# Master.net
KiCad netlist of a schematic drawn in EAGLE
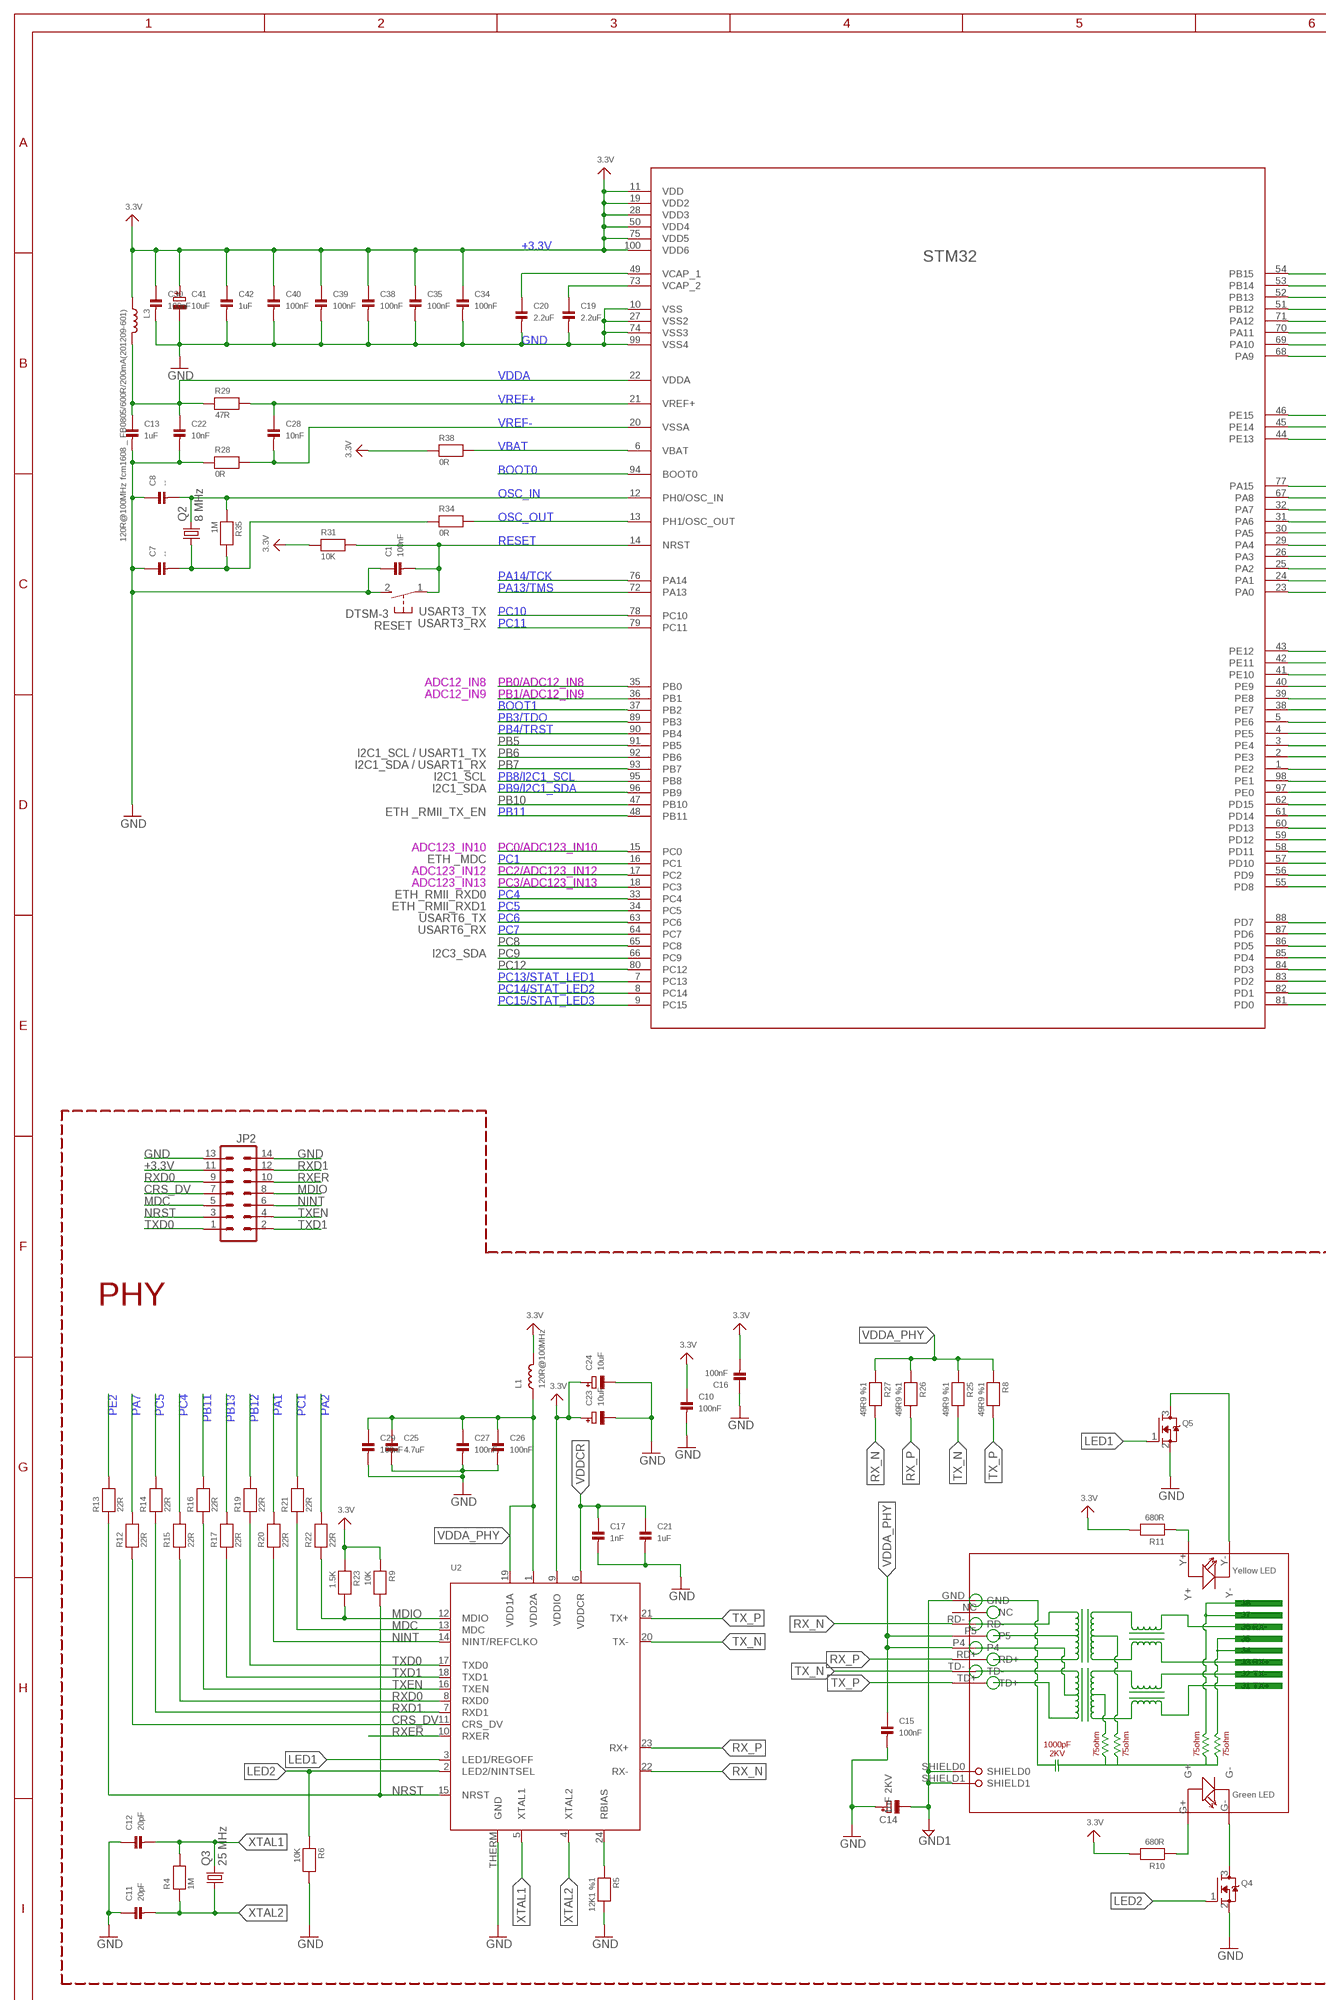
[diagram p0: schematic, sheet 1, part 1 of 2]
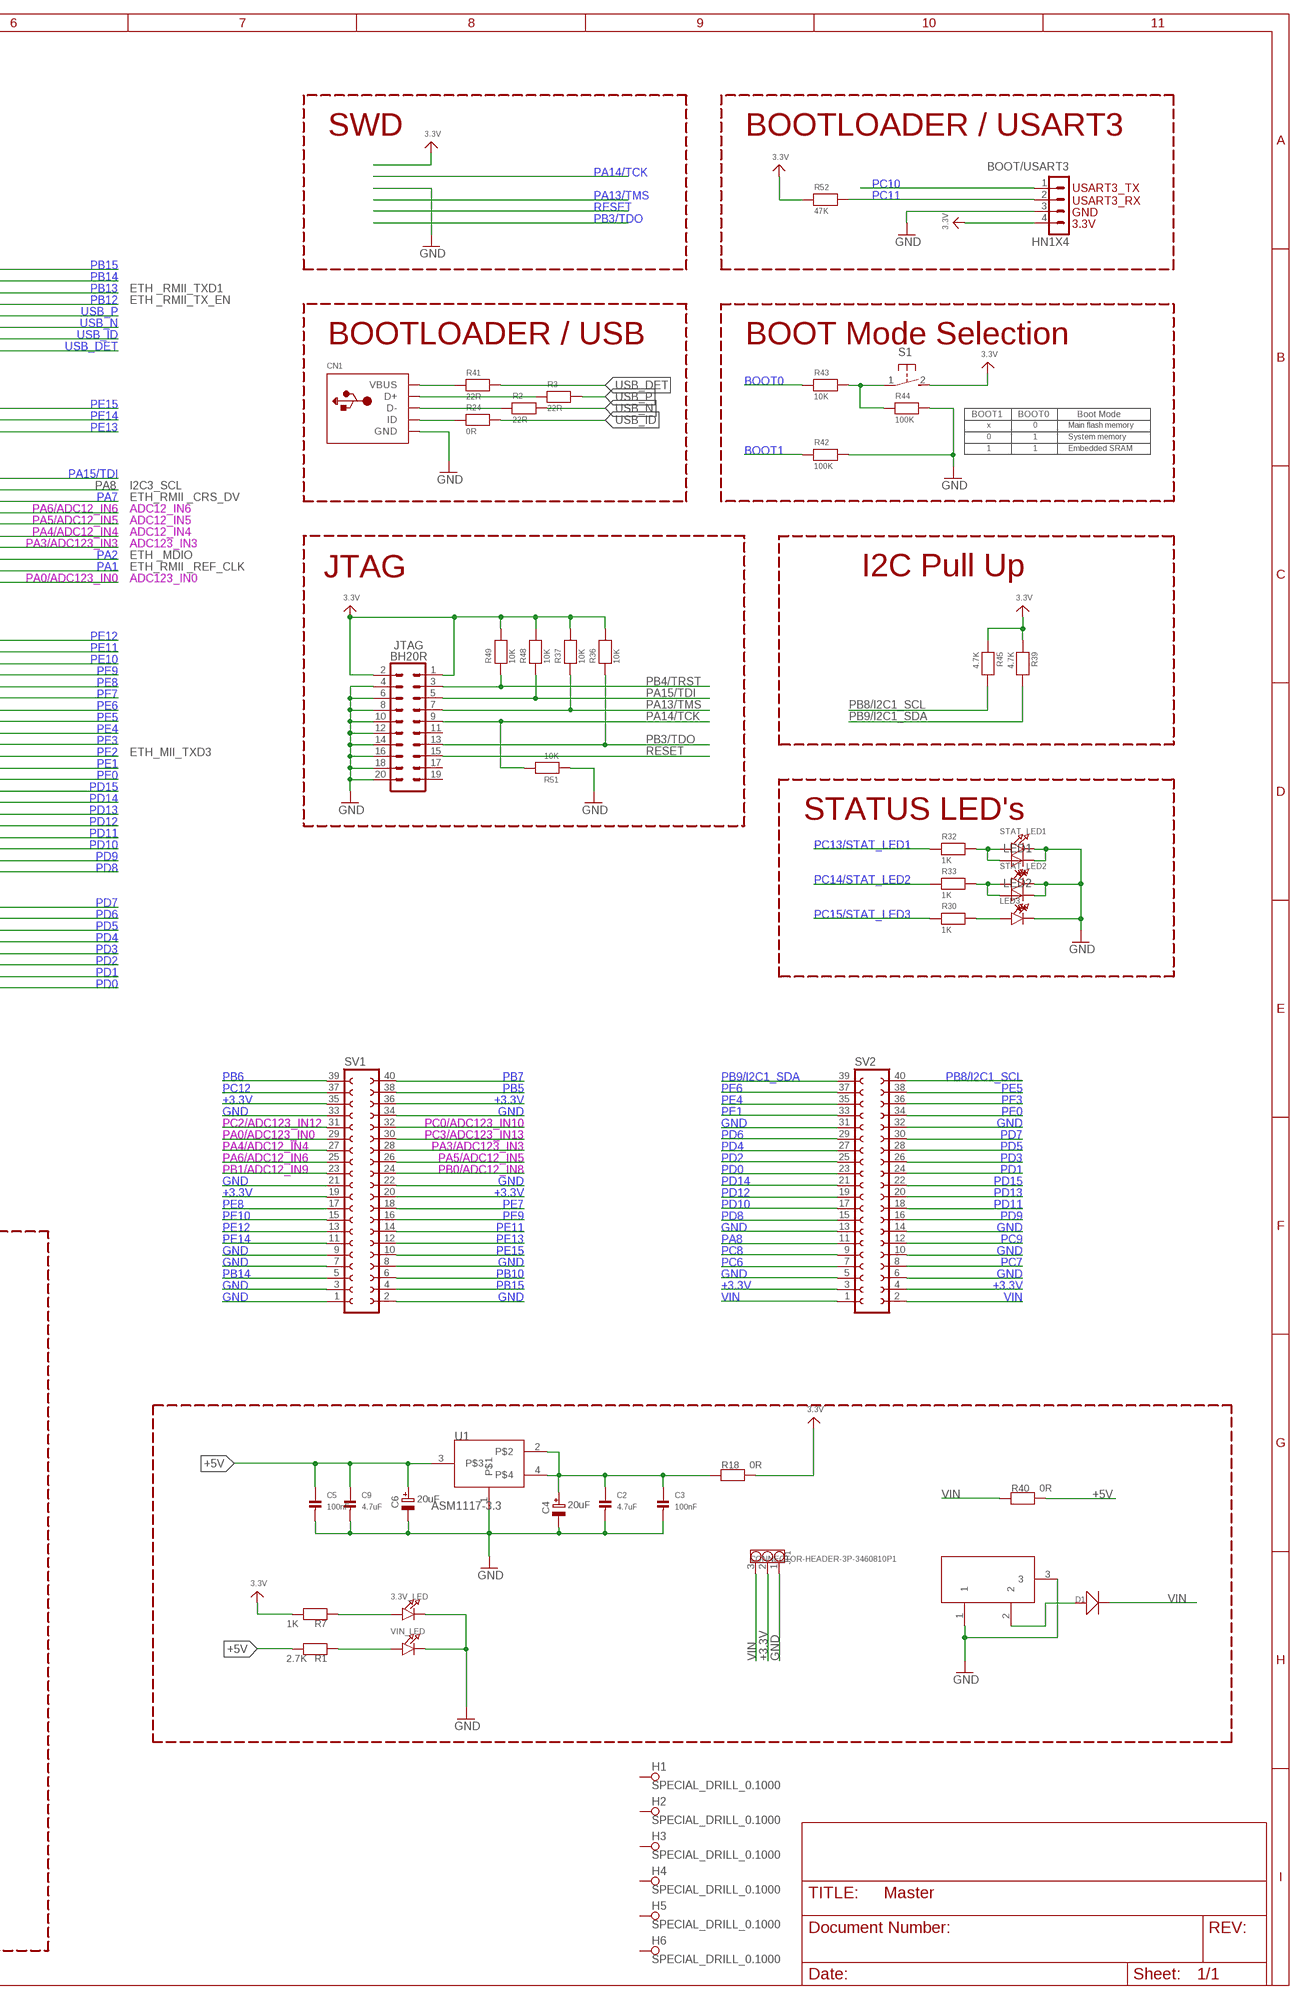
[diagram p1: schematic, sheet 1, part 2 of 2]

(export (version "E")
  (design (tool "Eeschema 10.0.6"))
  (components
    (comp (ref "3.3V_LED")
      (value "LED0805")
      (footprint "eagle-import:CHIPLED_0805")
      (libsource (lib "eagle-import") (part "LED0805"))
    )
    (comp (ref "BOOT/USART3")
      (value "HN1X4")
      (footprint "eagle-import:HN1X4")
      (libsource (lib "eagle-import") (part "CON4HN1X4"))
    )
    (comp (ref "C1")
      (value "100nF")
      (footprint "eagle-import:_0603")
      (libsource (lib "eagle-import") (part "CAP_CERAMIC_0603"))
    )
    (comp (ref "C2")
      (value "4.7uF")
      (footprint "eagle-import:0805")
      (libsource (lib "eagle-import") (part "CAP_CERAMIC0805"))
    )
    (comp (ref "C3")
      (value "100nF")
      (footprint "eagle-import:0805")
      (libsource (lib "eagle-import") (part "CAP_CERAMIC0805"))
    )
    (comp (ref "C4")
      (value "20uF")
      (footprint "eagle-import:EIA3528-21_B-R")
      (libsource (lib "eagle-import") (part "CAP_TANTALUMB/3528_REFLOW"))
    )
    (comp (ref "C5")
      (value "100nF")
      (footprint "eagle-import:0805")
      (libsource (lib "eagle-import") (part "CAP_CERAMIC0805"))
    )
    (comp (ref "C6")
      (value "20uF")
      (footprint "eagle-import:EIA3528-21_B-R")
      (libsource (lib "eagle-import") (part "CAP_TANTALUMB/3528_REFLOW"))
    )
    (comp (ref "C7")
      (value "--")
      (footprint "eagle-import:_0603")
      (libsource (lib "eagle-import") (part "CAP_CERAMIC_0603"))
    )
    (comp (ref "C8")
      (value "--")
      (footprint "eagle-import:_0603")
      (libsource (lib "eagle-import") (part "CAP_CERAMIC_0603"))
    )
    (comp (ref "C9")
      (value "4.7uF")
      (footprint "eagle-import:0805")
      (libsource (lib "eagle-import") (part "CAP_CERAMIC0805"))
    )
    (comp (ref "C10")
      (value "100nF")
      (footprint "eagle-import:_0603")
      (libsource (lib "eagle-import") (part "CAP_CERAMIC_0603"))
    )
    (comp (ref "C11")
      (value "20pF")
      (footprint "eagle-import:_0603")
      (libsource (lib "eagle-import") (part "CAP_CERAMIC_0603"))
    )
    (comp (ref "C12")
      (value "20pF")
      (footprint "eagle-import:_0603")
      (libsource (lib "eagle-import") (part "CAP_CERAMIC_0603"))
    )
    (comp (ref "C13")
      (value "1uF")
      (footprint "eagle-import:_0805")
      (libsource (lib "eagle-import") (part "CAP_CERAMIC_0805"))
    )
    (comp (ref "C14")
      (value "1nF 2KV")
      (footprint "eagle-import:EIA3528-21_B-R")
      (libsource (lib "eagle-import") (part "CAP_TANTALUMB/3528_REFLOW"))
    )
    (comp (ref "C15")
      (value "100nF")
      (footprint "eagle-import:_0805")
      (libsource (lib "eagle-import") (part "CAP_CERAMIC_0805"))
    )
    (comp (ref "C16")
      (value "100nF")
      (footprint "eagle-import:_0603")
      (libsource (lib "eagle-import") (part "CAP_CERAMIC_0603"))
    )
    (comp (ref "C17")
      (value "1nF")
      (footprint "eagle-import:_0603")
      (libsource (lib "eagle-import") (part "CAP_CERAMIC_0603"))
    )
    (comp (ref "C19")
      (value "2.2uF")
      (footprint "eagle-import:1206")
      (libsource (lib "eagle-import") (part "CAP_CERAMIC1206"))
    )
    (comp (ref "C20")
      (value "2.2uF")
      (footprint "eagle-import:1206")
      (libsource (lib "eagle-import") (part "CAP_CERAMIC1206"))
    )
    (comp (ref "C21")
      (value "1uF")
      (footprint "eagle-import:_0805")
      (libsource (lib "eagle-import") (part "CAP_CERAMIC_0805"))
    )
    (comp (ref "C22")
      (value "10nF")
      (footprint "eagle-import:_0603")
      (libsource (lib "eagle-import") (part "CAP_CERAMIC_0603"))
    )
    (comp (ref "C23")
      (value "10uF")
      (footprint "eagle-import:EIA3528-21_B-R")
      (libsource (lib "eagle-import") (part "CAP_TANTALUMB/3528_REFLOW"))
    )
    (comp (ref "C24")
      (value "10uF")
      (footprint "eagle-import:EIA3528-21_B-R")
      (libsource (lib "eagle-import") (part "CAP_TANTALUMB/3528_REFLOW"))
    )
    (comp (ref "C25")
      (value "4.7uF")
      (footprint "eagle-import:_0805")
      (libsource (lib "eagle-import") (part "CAP_CERAMIC_0805"))
    )
    (comp (ref "C26")
      (value "100nF")
      (footprint "eagle-import:_0603")
      (libsource (lib "eagle-import") (part "CAP_CERAMIC_0603"))
    )
    (comp (ref "C27")
      (value "100nF")
      (footprint "eagle-import:_0603")
      (libsource (lib "eagle-import") (part "CAP_CERAMIC_0603"))
    )
    (comp (ref "C28")
      (value "10nF")
      (footprint "eagle-import:_0603")
      (libsource (lib "eagle-import") (part "CAP_CERAMIC_0603"))
    )
    (comp (ref "C29")
      (value "100nF")
      (footprint "eagle-import:_0603")
      (libsource (lib "eagle-import") (part "CAP_CERAMIC_0603"))
    )
    (comp (ref "C30")
      (value "100nF")
      (footprint "eagle-import:_0603")
      (libsource (lib "eagle-import") (part "CAP_CERAMIC_0603"))
    )
    (comp (ref "C34")
      (value "100nF")
      (footprint "eagle-import:_0603")
      (libsource (lib "eagle-import") (part "CAP_CERAMIC_0603"))
    )
    (comp (ref "C35")
      (value "100nF")
      (footprint "eagle-import:_0603")
      (libsource (lib "eagle-import") (part "CAP_CERAMIC_0603"))
    )
    (comp (ref "C38")
      (value "100nF")
      (footprint "eagle-import:_0603")
      (libsource (lib "eagle-import") (part "CAP_CERAMIC_0603"))
    )
    (comp (ref "C39")
      (value "100nF")
      (footprint "eagle-import:_0603")
      (libsource (lib "eagle-import") (part "CAP_CERAMIC_0603"))
    )
    (comp (ref "C40")
      (value "100nF")
      (footprint "eagle-import:_0603")
      (libsource (lib "eagle-import") (part "CAP_CERAMIC_0603"))
    )
    (comp (ref "C41")
      (value "10uF")
      (footprint "eagle-import:EIA3528-21_B-R")
      (libsource (lib "eagle-import") (part "CAP_TANTALUMB/3528_REFLOW"))
    )
    (comp (ref "C42")
      (value "1uF")
      (footprint "eagle-import:_0805")
      (libsource (lib "eagle-import") (part "CAP_CERAMIC_0805"))
    )
    (comp (ref "CN1")
      (value "USBMINIBLARGE")
      (footprint "eagle-import:USB-MINIB_LARGER")
      (libsource (lib "eagle-import") (part "USBMINIBLARGE"))
    )
    (comp (ref "D1")
      (value "D-D1206")
      (footprint "eagle-import:LL-34")
      (libsource (lib "eagle-import") (part "D-D1206"))
    )
    (comp (ref "H1")
      (value "SPECIAL_DRILL_0.1000")
      (footprint "eagle-import:PAD_0.1000")
      (libsource (lib "eagle-import") (part "SPECIAL_DRILL_0.1000"))
    )
    (comp (ref "H2")
      (value "SPECIAL_DRILL_0.1000")
      (footprint "eagle-import:PAD_0.1000")
      (libsource (lib "eagle-import") (part "SPECIAL_DRILL_0.1000"))
    )
    (comp (ref "H3")
      (value "SPECIAL_DRILL_0.1000")
      (footprint "eagle-import:PAD_0.1000")
      (libsource (lib "eagle-import") (part "SPECIAL_DRILL_0.1000"))
    )
    (comp (ref "H4")
      (value "SPECIAL_DRILL_0.1000")
      (footprint "eagle-import:PAD_0.1000")
      (libsource (lib "eagle-import") (part "SPECIAL_DRILL_0.1000"))
    )
    (comp (ref "H5")
      (value "SPECIAL_DRILL_0.1000")
      (footprint "eagle-import:PAD_0.1000")
      (libsource (lib "eagle-import") (part "SPECIAL_DRILL_0.1000"))
    )
    (comp (ref "H6")
      (value "SPECIAL_DRILL_0.1000")
      (footprint "eagle-import:PAD_0.1000")
      (libsource (lib "eagle-import") (part "SPECIAL_DRILL_0.1000"))
    )
    (comp (ref "JP1")
      (value "CONNECTOR-HEADER-3P-3460810P1")
      (footprint "eagle-import:1X3P-2.54-2.54-11.6-3.0-BLACK-MALE")
      (libsource (lib "eagle-import") (part "CONNECTOR-HEADER-3P-3460810P1"))
    )
    (comp (ref "JP2")
      (value "MA07-2")
      (footprint "eagle-import:MA07-2")
      (libsource (lib "eagle-import") (part "MA07-2"))
    )
    (comp (ref "JTAG")
      (value "BH20R")
      (footprint "eagle-import:BH20R")
      (libsource (lib "eagle-import") (part "ML20R"))
    )
    (comp (ref "L1")
      (value "120R@100MHz")
      (footprint "eagle-import:_0805")
      (libsource (lib "eagle-import") (part "INDUCTOR_0805"))
    )
    (comp (ref "L3")
      (value "120R@100MHz fcm1608 _ FB0805/600R/200mA(201209-601)")
      (footprint "eagle-import:_0805")
      (libsource (lib "eagle-import") (part "INDUCTOR_0805"))
    )
    (comp (ref "LED1")
      (value "LED5MM")
      (footprint "eagle-import:LED5MM")
      (libsource (lib "eagle-import") (part "LED5MM"))
    )
    (comp (ref "LED2")
      (value "LED5MM")
      (footprint "eagle-import:LED5MM")
      (libsource (lib "eagle-import") (part "LED5MM"))
    )
    (comp (ref "LED3")
      (value "LED0805")
      (footprint "eagle-import:CHIPLED_0805")
      (libsource (lib "eagle-import") (part "LED0805"))
    )
    (comp (ref "Q2")
      (value "8 MHz")
      (footprint "eagle-import:HC49UP")
      (libsource (lib "eagle-import") (part "CRYSTALHC49UP"))
    )
    (comp (ref "Q3")
      (value "25 MHz")
      (footprint "eagle-import:HC49UP")
      (libsource (lib "eagle-import") (part "CRYSTALHC49UP"))
    )
    (comp (ref "Q4")
      (value "MOSFET-NWIDE")
      (footprint "eagle-import:SOT23-WIDE")
      (libsource (lib "eagle-import") (part "MOSFET-NWIDE"))
    )
    (comp (ref "Q5")
      (value "MOSFET-NWIDE")
      (footprint "eagle-import:SOT23-WIDE")
      (libsource (lib "eagle-import") (part "MOSFET-NWIDE"))
    )
    (comp (ref "R1")
      (value "2.7K")
      (footprint "eagle-import:_0603")
      (libsource (lib "eagle-import") (part "RESISTOR_0603"))
    )
    (comp (ref "R2")
      (value "22R")
      (footprint "eagle-import:_0603")
      (libsource (lib "eagle-import") (part "RESISTOR_0603"))
    )
    (comp (ref "R3")
      (value "22R")
      (footprint "eagle-import:_0603")
      (libsource (lib "eagle-import") (part "RESISTOR_0603"))
    )
    (comp (ref "R4")
      (value "1M")
      (footprint "eagle-import:_0603")
      (libsource (lib "eagle-import") (part "RESISTOR_0603"))
    )
    (comp (ref "R5")
      (value "12K1 %1")
      (footprint "eagle-import:_0603")
      (libsource (lib "eagle-import") (part "RESISTOR_0603"))
    )
    (comp (ref "R6")
      (value "10K")
      (footprint "eagle-import:_0603")
      (libsource (lib "eagle-import") (part "RESISTOR_0603"))
    )
    (comp (ref "R7")
      (value "1K")
      (footprint "eagle-import:_0603")
      (libsource (lib "eagle-import") (part "RESISTOR_0603"))
    )
    (comp (ref "R8")
      (value "49R9 %1")
      (footprint "eagle-import:_0603")
      (libsource (lib "eagle-import") (part "RESISTOR_0603"))
    )
    (comp (ref "R9")
      (value "10K")
      (footprint "eagle-import:_0603")
      (libsource (lib "eagle-import") (part "RESISTOR_0603"))
    )
    (comp (ref "R10")
      (value "680R")
      (footprint "eagle-import:_0805")
      (libsource (lib "eagle-import") (part "RESISTOR_0805"))
    )
    (comp (ref "R11")
      (value "680R")
      (footprint "eagle-import:_0805")
      (libsource (lib "eagle-import") (part "RESISTOR_0805"))
    )
    (comp (ref "R12")
      (value "22R")
      (footprint "eagle-import:_0603")
      (libsource (lib "eagle-import") (part "RESISTOR_0603"))
    )
    (comp (ref "R13")
      (value "22R")
      (footprint "eagle-import:_0603")
      (libsource (lib "eagle-import") (part "RESISTOR_0603"))
    )
    (comp (ref "R14")
      (value "22R")
      (footprint "eagle-import:_0603")
      (libsource (lib "eagle-import") (part "RESISTOR_0603"))
    )
    (comp (ref "R15")
      (value "22R")
      (footprint "eagle-import:_0603")
      (libsource (lib "eagle-import") (part "RESISTOR_0603"))
    )
    (comp (ref "R16")
      (value "22R")
      (footprint "eagle-import:_0603")
      (libsource (lib "eagle-import") (part "RESISTOR_0603"))
    )
    (comp (ref "R17")
      (value "22R")
      (footprint "eagle-import:_0603")
      (libsource (lib "eagle-import") (part "RESISTOR_0603"))
    )
    (comp (ref "R18")
      (value "0R")
      (footprint "eagle-import:0805")
      (libsource (lib "eagle-import") (part "RESISTOR0805"))
    )
    (comp (ref "R19")
      (value "22R")
      (footprint "eagle-import:_0603")
      (libsource (lib "eagle-import") (part "RESISTOR_0603"))
    )
    (comp (ref "R20")
      (value "22R")
      (footprint "eagle-import:_0603")
      (libsource (lib "eagle-import") (part "RESISTOR_0603"))
    )
    (comp (ref "R21")
      (value "22R")
      (footprint "eagle-import:_0603")
      (libsource (lib "eagle-import") (part "RESISTOR_0603"))
    )
    (comp (ref "R22")
      (value "22R")
      (footprint "eagle-import:_0603")
      (libsource (lib "eagle-import") (part "RESISTOR_0603"))
    )
    (comp (ref "R23")
      (value "1.5K")
      (footprint "eagle-import:_0603")
      (libsource (lib "eagle-import") (part "RESISTOR_0603"))
    )
    (comp (ref "R24")
      (value "0R")
      (footprint "eagle-import:_0603")
      (libsource (lib "eagle-import") (part "RESISTOR_0603"))
    )
    (comp (ref "R25")
      (value "49R9 %1")
      (footprint "eagle-import:_0603")
      (libsource (lib "eagle-import") (part "RESISTOR_0603"))
    )
    (comp (ref "R26")
      (value "49R9 %1")
      (footprint "eagle-import:_0603")
      (libsource (lib "eagle-import") (part "RESISTOR_0603"))
    )
    (comp (ref "R27")
      (value "49R9 %1")
      (footprint "eagle-import:_0603")
      (libsource (lib "eagle-import") (part "RESISTOR_0603"))
    )
    (comp (ref "R28")
      (value "0R")
      (footprint "eagle-import:_0603")
      (libsource (lib "eagle-import") (part "RESISTOR_0603"))
    )
    (comp (ref "R29")
      (value "47R")
      (footprint "eagle-import:_0603")
      (libsource (lib "eagle-import") (part "RESISTOR_0603"))
    )
    (comp (ref "R30")
      (value "1K")
      (footprint "eagle-import:_0603")
      (libsource (lib "eagle-import") (part "RESISTOR_0603"))
    )
    (comp (ref "R31")
      (value "10K")
      (footprint "eagle-import:_0603")
      (libsource (lib "eagle-import") (part "RESISTOR_0603"))
    )
    (comp (ref "R32")
      (value "1K")
      (footprint "eagle-import:_0603")
      (libsource (lib "eagle-import") (part "RESISTOR_0603"))
    )
    (comp (ref "R33")
      (value "1K")
      (footprint "eagle-import:_0603")
      (libsource (lib "eagle-import") (part "RESISTOR_0603"))
    )
    (comp (ref "R34")
      (value "0R")
      (footprint "eagle-import:_0603")
      (libsource (lib "eagle-import") (part "RESISTOR_0603"))
    )
    (comp (ref "R35")
      (value "1M")
      (footprint "eagle-import:_0603")
      (libsource (lib "eagle-import") (part "RESISTOR_0603"))
    )
    (comp (ref "R36")
      (value "10K")
      (footprint "eagle-import:_0603")
      (libsource (lib "eagle-import") (part "RESISTOR_0603"))
    )
    (comp (ref "R37")
      (value "10K")
      (footprint "eagle-import:_0603")
      (libsource (lib "eagle-import") (part "RESISTOR_0603"))
    )
    (comp (ref "R38")
      (value "0R")
      (footprint "eagle-import:_0603")
      (libsource (lib "eagle-import") (part "RESISTOR_0603"))
    )
    (comp (ref "R39")
      (value "4.7K")
      (footprint "eagle-import:1206")
      (libsource (lib "eagle-import") (part "RESISTOR1206"))
    )
    (comp (ref "R40")
      (value "0R")
      (footprint "eagle-import:0805")
      (libsource (lib "eagle-import") (part "RESISTOR0805"))
    )
    (comp (ref "R41")
      (value "22R")
      (footprint "eagle-import:_0603")
      (libsource (lib "eagle-import") (part "RESISTOR_0603"))
    )
    (comp (ref "R42")
      (value "100K")
      (footprint "eagle-import:_0603")
      (libsource (lib "eagle-import") (part "RESISTOR_0603"))
    )
    (comp (ref "R43")
      (value "10K")
      (footprint "eagle-import:_0603")
      (libsource (lib "eagle-import") (part "RESISTOR_0603"))
    )
    (comp (ref "R44")
      (value "100K")
      (footprint "eagle-import:_0603")
      (libsource (lib "eagle-import") (part "RESISTOR_0603"))
    )
    (comp (ref "R45")
      (value "4.7K")
      (footprint "eagle-import:1206")
      (libsource (lib "eagle-import") (part "RESISTOR1206"))
    )
    (comp (ref "R48")
      (value "10K")
      (footprint "eagle-import:_0603")
      (libsource (lib "eagle-import") (part "RESISTOR_0603"))
    )
    (comp (ref "R49")
      (value "10K")
      (footprint "eagle-import:_0603")
      (libsource (lib "eagle-import") (part "RESISTOR_0603"))
    )
    (comp (ref "R51")
      (value "10K")
      (footprint "eagle-import:_0603")
      (libsource (lib "eagle-import") (part "RESISTOR_0603"))
    )
    (comp (ref "R52")
      (value "47K")
      (footprint "eagle-import:_0603")
      (libsource (lib "eagle-import") (part "RESISTOR_0603"))
    )
    (comp (ref "RESET")
      (value "DTSM-3")
      (footprint "eagle-import:DTSM-3")
      (libsource (lib "eagle-import") (part "DTSM-3"))
    )
    (comp (ref "RJ1")
      (value "HR911105A")
      (footprint "eagle-import:HR911105A")
      (libsource (lib "eagle-import") (part "HR911105A"))
    )
    (comp (ref "S1")
      (value "31-XX")
      (footprint "eagle-import:B3F-31XX")
      (fields (field (name "MPN") "B3F-3100"))
      (libsource (lib "eagle-import") (part "31-XX"))
    )
    (comp (ref "STAT_LED1")
      (value "LED0805")
      (footprint "eagle-import:CHIPLED_0805")
      (libsource (lib "eagle-import") (part "LED0805"))
    )
    (comp (ref "STAT_LED2")
      (value "LED0805")
      (footprint "eagle-import:CHIPLED_0805")
      (libsource (lib "eagle-import") (part "LED0805"))
    )
    (comp (ref "STM32")
      (value "STM32F407")
      (footprint "eagle-import:100LQFP")
      (libsource (lib "eagle-import") (part "STM32F407"))
    )
    (comp (ref "SV1")
      (value "FE20-2")
      (footprint "eagle-import:FE20-2")
      (libsource (lib "eagle-import") (part "FE20-2"))
    )
    (comp (ref "SV2")
      (value "FE20-2")
      (footprint "eagle-import:FE20-2")
      (libsource (lib "eagle-import") (part "FE20-2"))
    )
    (comp (ref "U1")
      (value "ASM1117-3.3")
      (footprint "eagle-import:SOT223")
      (libsource (lib "eagle-import") (part "ASM1117-3.3"))
    )
    (comp (ref "U2")
      (value "LAN8720")
      (footprint "eagle-import:QFN24_4MM")
      (libsource (lib "eagle-import") (part "LAN8720"))
    )
    (comp (ref "VIN_LED")
      (value "LED0805")
      (footprint "eagle-import:CHIPLED_0805")
      (libsource (lib "eagle-import") (part "LED0805"))
    )
    (comp (ref "X1")
      (value "DC21MMX")
      (footprint "eagle-import:DC-21MM")
      (libsource (lib "eagle-import") (part "DC21MMX"))
    )
  )
  (nets
    (net (code "1") (name "+5V") (class "Default")
      (node (ref "C5") (pin "1") (pinfunction "P$1_1") (pintype "passive"))
      (node (ref "C6") (pin "+") (pinfunction "+_+") (pintype "passive"))
      (node (ref "C9") (pin "1") (pinfunction "P$1_1") (pintype "passive"))
      (node (ref "R1") (pin "2") (pinfunction "2_2") (pintype "passive"))
      (node (ref "R40") (pin "2") (pinfunction "2_2") (pintype "passive"))
      (node (ref "U1") (pin "3") (pinfunction "P$3_3") (pintype "bidirectional"))
    )
    (net (code "2") (name "/BOOT0") (class "Default")
      (node (ref "R43") (pin "1") (pinfunction "1_1") (pintype "passive"))
      (node (ref "STM32") (pin "94") (pinfunction "BOOT0_94") (pintype "bidirectional"))
    )
    (net (code "3") (name "/BOOT1") (class "Default")
      (node (ref "R42") (pin "1") (pinfunction "1_1") (pintype "passive"))
      (node (ref "STM32") (pin "37") (pinfunction "PB2_37") (pintype "bidirectional"))
    )
    (net (code "4") (name "/CRS_DV") (class "Default")
      (node (ref "JP2") (pin "7") (pinfunction "7_7") (pintype "passive"))
      (node (ref "R12") (pin "1") (pinfunction "1_1") (pintype "passive"))
      (node (ref "U2") (pin "11") (pinfunction "CRS_DV_11") (pintype "bidirectional"))
    )
    (net (code "5") (name "/MDC") (class "Default")
      (node (ref "JP2") (pin "5") (pinfunction "5_5") (pintype "passive"))
      (node (ref "R21") (pin "1") (pinfunction "1_1") (pintype "passive"))
      (node (ref "U2") (pin "13") (pinfunction "MDC_13") (pintype "bidirectional"))
    )
    (net (code "6") (name "/MDIO") (class "Default")
      (node (ref "JP2") (pin "8") (pinfunction "8_8") (pintype "passive"))
      (node (ref "R22") (pin "1") (pinfunction "1_1") (pintype "passive"))
      (node (ref "R23") (pin "2") (pinfunction "2_2") (pintype "passive"))
      (node (ref "U2") (pin "12") (pinfunction "MDIO_12") (pintype "bidirectional"))
    )
    (net (code "7") (name "/NINT") (class "Default")
      (node (ref "JP2") (pin "6") (pinfunction "6_6") (pintype "passive"))
      (node (ref "R20") (pin "1") (pinfunction "1_1") (pintype "passive"))
      (node (ref "U2") (pin "14") (pinfunction "NINT/REFCLKO_14") (pintype "bidirectional"))
    )
    (net (code "8") (name "/NRST") (class "Default")
      (node (ref "JP2") (pin "3") (pinfunction "3_3") (pintype "passive"))
      (node (ref "R13") (pin "1") (pinfunction "1_1") (pintype "passive"))
      (node (ref "R9") (pin "2") (pinfunction "2_2") (pintype "passive"))
      (node (ref "U2") (pin "15") (pinfunction "NRST_15") (pintype "bidirectional"))
    )
    (net (code "9") (name "/OSC_IN") (class "Default")
      (node (ref "C8") (pin "2") (pinfunction "P$2_2") (pintype "passive"))
      (node (ref "Q2") (pin "2") (pinfunction "2_2") (pintype "passive"))
      (node (ref "R35") (pin "1") (pinfunction "1_1") (pintype "passive"))
      (node (ref "STM32") (pin "12") (pinfunction "PH0/OSC_IN_12") (pintype "bidirectional"))
    )
    (net (code "10") (name "/OSC_OUT") (class "Default")
      (node (ref "R34") (pin "2") (pinfunction "2_2") (pintype "passive"))
      (node (ref "STM32") (pin "13") (pinfunction "PH1/OSC_OUT_13") (pintype "bidirectional"))
    )
    (net (code "11") (name "/PA0{slash}ADC123_IN0") (class "Default")
      (node (ref "STM32") (pin "23") (pinfunction "PA0_23") (pintype "bidirectional"))
      (node (ref "SV1") (pin "29") (pinfunction "29_29") (pintype "passive"))
    )
    (net (code "12") (name "/PA1") (class "Default")
      (node (ref "R20") (pin "2") (pinfunction "2_2") (pintype "passive"))
      (node (ref "STM32") (pin "24") (pinfunction "PA1_24") (pintype "bidirectional"))
    )
    (net (code "13") (name "/PA2") (class "Default")
      (node (ref "R22") (pin "2") (pinfunction "2_2") (pintype "passive"))
      (node (ref "STM32") (pin "25") (pinfunction "PA2_25") (pintype "bidirectional"))
    )
    (net (code "14") (name "/PA3{slash}ADC123_IN3") (class "Default")
      (node (ref "STM32") (pin "26") (pinfunction "PA3_26") (pintype "bidirectional"))
      (node (ref "SV1") (pin "28") (pinfunction "28_28") (pintype "passive"))
    )
    (net (code "15") (name "/PA4{slash}ADC12_IN4") (class "Default")
      (node (ref "STM32") (pin "29") (pinfunction "PA4_29") (pintype "bidirectional"))
      (node (ref "SV1") (pin "27") (pinfunction "27_27") (pintype "passive"))
    )
    (net (code "16") (name "/PA5{slash}ADC12_IN5") (class "Default")
      (node (ref "STM32") (pin "30") (pinfunction "PA5_30") (pintype "bidirectional"))
      (node (ref "SV1") (pin "26") (pinfunction "26_26") (pintype "passive"))
    )
    (net (code "17") (name "/PA6{slash}ADC12_IN6") (class "Default")
      (node (ref "STM32") (pin "31") (pinfunction "PA6_31") (pintype "bidirectional"))
      (node (ref "SV1") (pin "25") (pinfunction "25_25") (pintype "passive"))
    )
    (net (code "18") (name "/PA7") (class "Default")
      (node (ref "R12") (pin "2") (pinfunction "2_2") (pintype "passive"))
      (node (ref "STM32") (pin "32") (pinfunction "PA7_32") (pintype "bidirectional"))
    )
    (net (code "19") (name "/PA8") (class "Default")
      (node (ref "STM32") (pin "67") (pinfunction "PA8_67") (pintype "bidirectional"))
      (node (ref "SV2") (pin "11") (pinfunction "11_11") (pintype "passive"))
    )
    (net (code "20") (name "/PA13{slash}TMS") (class "Default")
      (node (ref "JTAG") (pin "7") (pinfunction "7_7") (pintype "passive"))
      (node (ref "R37") (pin "1") (pinfunction "1_1") (pintype "passive"))
      (node (ref "STM32") (pin "72") (pinfunction "PA13_72") (pintype "bidirectional"))
    )
    (net (code "21") (name "/PA14{slash}TCK") (class "Default")
      (node (ref "JTAG") (pin "9") (pinfunction "9_9") (pintype "passive"))
      (node (ref "R51") (pin "2") (pinfunction "2_2") (pintype "passive"))
      (node (ref "STM32") (pin "76") (pinfunction "PA14_76") (pintype "bidirectional"))
    )
    (net (code "22") (name "/PA15{slash}TDI") (class "Default")
      (node (ref "JTAG") (pin "5") (pinfunction "5_5") (pintype "passive"))
      (node (ref "R48") (pin "1") (pinfunction "1_1") (pintype "passive"))
      (node (ref "STM32") (pin "77") (pinfunction "PA15_77") (pintype "bidirectional"))
    )
    (net (code "23") (name "/PB0{slash}ADC12_IN8") (class "Default")
      (node (ref "STM32") (pin "35") (pinfunction "PB0_35") (pintype "bidirectional"))
      (node (ref "SV1") (pin "24") (pinfunction "24_24") (pintype "passive"))
    )
    (net (code "24") (name "/PB1{slash}ADC12_IN9") (class "Default")
      (node (ref "STM32") (pin "36") (pinfunction "PB1_36") (pintype "bidirectional"))
      (node (ref "SV1") (pin "23") (pinfunction "23_23") (pintype "passive"))
    )
    (net (code "25") (name "/PB3{slash}TDO") (class "Default")
      (node (ref "JTAG") (pin "13") (pinfunction "13_13") (pintype "passive"))
      (node (ref "R36") (pin "1") (pinfunction "1_1") (pintype "passive"))
      (node (ref "STM32") (pin "89") (pinfunction "PB3_89") (pintype "bidirectional"))
    )
    (net (code "26") (name "/PB4{slash}TRST") (class "Default")
      (node (ref "JTAG") (pin "3") (pinfunction "3_3") (pintype "passive"))
      (node (ref "R49") (pin "1") (pinfunction "1_1") (pintype "passive"))
      (node (ref "STM32") (pin "90") (pinfunction "PB4_90") (pintype "bidirectional"))
    )
    (net (code "27") (name "/PB5") (class "Default")
      (node (ref "STM32") (pin "91") (pinfunction "PB5_91") (pintype "bidirectional"))
      (node (ref "SV1") (pin "38") (pinfunction "38_38") (pintype "passive"))
    )
    (net (code "28") (name "/PB6") (class "Default")
      (node (ref "STM32") (pin "92") (pinfunction "PB6_92") (pintype "bidirectional"))
      (node (ref "SV1") (pin "39") (pinfunction "39_39") (pintype "passive"))
    )
    (net (code "29") (name "/PB7") (class "Default")
      (node (ref "STM32") (pin "93") (pinfunction "PB7_93") (pintype "bidirectional"))
      (node (ref "SV1") (pin "40") (pinfunction "40_40") (pintype "passive"))
    )
    (net (code "30") (name "/PB8{slash}I2C1_SCL") (class "Default")
      (node (ref "R45") (pin "2") (pinfunction "2_2") (pintype "passive"))
      (node (ref "STM32") (pin "95") (pinfunction "PB8_95") (pintype "bidirectional"))
      (node (ref "SV2") (pin "40") (pinfunction "40_40") (pintype "passive"))
    )
    (net (code "31") (name "/PB9{slash}I2C1_SDA") (class "Default")
      (node (ref "R39") (pin "2") (pinfunction "2_2") (pintype "passive"))
      (node (ref "STM32") (pin "96") (pinfunction "PB9_96") (pintype "bidirectional"))
      (node (ref "SV2") (pin "39") (pinfunction "39_39") (pintype "passive"))
    )
    (net (code "32") (name "/PB10") (class "Default")
      (node (ref "STM32") (pin "47") (pinfunction "PB10_47") (pintype "bidirectional"))
      (node (ref "SV1") (pin "6") (pinfunction "6_6") (pintype "passive"))
    )
    (net (code "33") (name "/PB11") (class "Default")
      (node (ref "R16") (pin "2") (pinfunction "2_2") (pintype "passive"))
      (node (ref "STM32") (pin "48") (pinfunction "PB11_48") (pintype "bidirectional"))
    )
    (net (code "34") (name "/PB12") (class "Default")
      (node (ref "R19") (pin "2") (pinfunction "2_2") (pintype "passive"))
      (node (ref "STM32") (pin "51") (pinfunction "PB12_51") (pintype "bidirectional"))
    )
    (net (code "35") (name "/PB13") (class "Default")
      (node (ref "R17") (pin "2") (pinfunction "2_2") (pintype "passive"))
      (node (ref "STM32") (pin "52") (pinfunction "PB13_52") (pintype "bidirectional"))
    )
    (net (code "36") (name "/PB14") (class "Default")
      (node (ref "STM32") (pin "53") (pinfunction "PB14_53") (pintype "bidirectional"))
      (node (ref "SV1") (pin "5") (pinfunction "5_5") (pintype "passive"))
    )
    (net (code "37") (name "/PB15") (class "Default")
      (node (ref "STM32") (pin "54") (pinfunction "PB15_54") (pintype "bidirectional"))
      (node (ref "SV1") (pin "4") (pinfunction "4_4") (pintype "passive"))
    )
    (net (code "38") (name "/PC0{slash}ADC123_IN10") (class "Default")
      (node (ref "STM32") (pin "15") (pinfunction "PC0_15") (pintype "bidirectional"))
      (node (ref "SV1") (pin "32") (pinfunction "32_32") (pintype "passive"))
    )
    (net (code "39") (name "/PC1") (class "Default")
      (node (ref "R21") (pin "2") (pinfunction "2_2") (pintype "passive"))
      (node (ref "STM32") (pin "16") (pinfunction "PC1_16") (pintype "bidirectional"))
    )
    (net (code "40") (name "/PC2{slash}ADC123_IN12") (class "Default")
      (node (ref "STM32") (pin "17") (pinfunction "PC2_17") (pintype "bidirectional"))
      (node (ref "SV1") (pin "31") (pinfunction "31_31") (pintype "passive"))
    )
    (net (code "41") (name "/PC3{slash}ADC123_IN13") (class "Default")
      (node (ref "STM32") (pin "18") (pinfunction "PC3_18") (pintype "bidirectional"))
      (node (ref "SV1") (pin "30") (pinfunction "30_30") (pintype "passive"))
    )
    (net (code "42") (name "/PC4") (class "Default")
      (node (ref "R15") (pin "2") (pinfunction "2_2") (pintype "passive"))
      (node (ref "STM32") (pin "33") (pinfunction "PC4_33") (pintype "bidirectional"))
    )
    (net (code "43") (name "/PC5") (class "Default")
      (node (ref "R14") (pin "2") (pinfunction "2_2") (pintype "passive"))
      (node (ref "STM32") (pin "34") (pinfunction "PC5_34") (pintype "bidirectional"))
    )
    (net (code "44") (name "/PC6") (class "Default")
      (node (ref "STM32") (pin "63") (pinfunction "PC6_63") (pintype "bidirectional"))
      (node (ref "SV2") (pin "7") (pinfunction "7_7") (pintype "passive"))
    )
    (net (code "45") (name "/PC7") (class "Default")
      (node (ref "STM32") (pin "64") (pinfunction "PC7_64") (pintype "bidirectional"))
      (node (ref "SV2") (pin "8") (pinfunction "8_8") (pintype "passive"))
    )
    (net (code "46") (name "/PC8") (class "Default")
      (node (ref "STM32") (pin "65") (pinfunction "PC8_65") (pintype "bidirectional"))
      (node (ref "SV2") (pin "9") (pinfunction "9_9") (pintype "passive"))
    )
    (net (code "47") (name "/PC9") (class "Default")
      (node (ref "STM32") (pin "66") (pinfunction "PC9_66") (pintype "bidirectional"))
      (node (ref "SV2") (pin "12") (pinfunction "12_12") (pintype "passive"))
    )
    (net (code "48") (name "/PC10") (class "Default")
      (node (ref "BOOT/USART3") (pin "1") (pinfunction "1_1") (pintype "passive"))
      (node (ref "STM32") (pin "78") (pinfunction "PC10_78") (pintype "bidirectional"))
    )
    (net (code "49") (name "/PC11") (class "Default")
      (node (ref "BOOT/USART3") (pin "2") (pinfunction "2_2") (pintype "passive"))
      (node (ref "R52") (pin "2") (pinfunction "2_2") (pintype "passive"))
      (node (ref "STM32") (pin "79") (pinfunction "PC11_79") (pintype "bidirectional"))
    )
    (net (code "50") (name "/PC12") (class "Default")
      (node (ref "STM32") (pin "80") (pinfunction "PC12_80") (pintype "bidirectional"))
      (node (ref "SV1") (pin "37") (pinfunction "37_37") (pintype "passive"))
    )
    (net (code "51") (name "/PC13{slash}STAT_LED1") (class "Default")
      (node (ref "R32") (pin "1") (pinfunction "1_1") (pintype "passive"))
      (node (ref "STM32") (pin "7") (pinfunction "PC13_7") (pintype "bidirectional"))
    )
    (net (code "52") (name "/PC14{slash}STAT_LED2") (class "Default")
      (node (ref "R33") (pin "1") (pinfunction "1_1") (pintype "passive"))
      (node (ref "STM32") (pin "8") (pinfunction "PC14_8") (pintype "bidirectional"))
    )
    (net (code "53") (name "/PC15{slash}STAT_LED3") (class "Default")
      (node (ref "R30") (pin "1") (pinfunction "1_1") (pintype "passive"))
      (node (ref "STM32") (pin "9") (pinfunction "PC15_9") (pintype "bidirectional"))
    )
    (net (code "54") (name "/PD0") (class "Default")
      (node (ref "STM32") (pin "81") (pinfunction "PD0_81") (pintype "bidirectional"))
      (node (ref "SV2") (pin "23") (pinfunction "23_23") (pintype "passive"))
    )
    (net (code "55") (name "/PD1") (class "Default")
      (node (ref "STM32") (pin "82") (pinfunction "PD1_82") (pintype "bidirectional"))
      (node (ref "SV2") (pin "24") (pinfunction "24_24") (pintype "passive"))
    )
    (net (code "56") (name "/PD2") (class "Default")
      (node (ref "STM32") (pin "83") (pinfunction "PD2_83") (pintype "bidirectional"))
      (node (ref "SV2") (pin "25") (pinfunction "25_25") (pintype "passive"))
    )
    (net (code "57") (name "/PD3") (class "Default")
      (node (ref "STM32") (pin "84") (pinfunction "PD3_84") (pintype "bidirectional"))
      (node (ref "SV2") (pin "26") (pinfunction "26_26") (pintype "passive"))
    )
    (net (code "58") (name "/PD4") (class "Default")
      (node (ref "STM32") (pin "85") (pinfunction "PD4_85") (pintype "bidirectional"))
      (node (ref "SV2") (pin "27") (pinfunction "27_27") (pintype "passive"))
    )
    (net (code "59") (name "/PD5") (class "Default")
      (node (ref "STM32") (pin "86") (pinfunction "PD5_86") (pintype "bidirectional"))
      (node (ref "SV2") (pin "28") (pinfunction "28_28") (pintype "passive"))
    )
    (net (code "60") (name "/PD6") (class "Default")
      (node (ref "STM32") (pin "87") (pinfunction "PD6_87") (pintype "bidirectional"))
      (node (ref "SV2") (pin "29") (pinfunction "29_29") (pintype "passive"))
    )
    (net (code "61") (name "/PD7") (class "Default")
      (node (ref "STM32") (pin "88") (pinfunction "PD7_88") (pintype "bidirectional"))
      (node (ref "SV2") (pin "30") (pinfunction "30_30") (pintype "passive"))
    )
    (net (code "62") (name "/PD8") (class "Default")
      (node (ref "STM32") (pin "55") (pinfunction "PD8_55") (pintype "bidirectional"))
      (node (ref "SV2") (pin "15") (pinfunction "15_15") (pintype "passive"))
    )
    (net (code "63") (name "/PD9") (class "Default")
      (node (ref "STM32") (pin "56") (pinfunction "PD9_56") (pintype "bidirectional"))
      (node (ref "SV2") (pin "16") (pinfunction "16_16") (pintype "passive"))
    )
    (net (code "64") (name "/PD10") (class "Default")
      (node (ref "STM32") (pin "57") (pinfunction "PD10_57") (pintype "bidirectional"))
      (node (ref "SV2") (pin "17") (pinfunction "17_17") (pintype "passive"))
    )
    (net (code "65") (name "/PD11") (class "Default")
      (node (ref "STM32") (pin "58") (pinfunction "PD11_58") (pintype "bidirectional"))
      (node (ref "SV2") (pin "18") (pinfunction "18_18") (pintype "passive"))
    )
    (net (code "66") (name "/PD12") (class "Default")
      (node (ref "STM32") (pin "59") (pinfunction "PD12_59") (pintype "bidirectional"))
      (node (ref "SV2") (pin "19") (pinfunction "19_19") (pintype "passive"))
    )
    (net (code "67") (name "/PD13") (class "Default")
      (node (ref "STM32") (pin "60") (pinfunction "PD13_60") (pintype "bidirectional"))
      (node (ref "SV2") (pin "20") (pinfunction "20_20") (pintype "passive"))
    )
    (net (code "68") (name "/PD14") (class "Default")
      (node (ref "STM32") (pin "61") (pinfunction "PD14_61") (pintype "bidirectional"))
      (node (ref "SV2") (pin "21") (pinfunction "21_21") (pintype "passive"))
    )
    (net (code "69") (name "/PD15") (class "Default")
      (node (ref "STM32") (pin "62") (pinfunction "PD15_62") (pintype "bidirectional"))
      (node (ref "SV2") (pin "22") (pinfunction "22_22") (pintype "passive"))
    )
    (net (code "70") (name "/PE0") (class "Default")
      (node (ref "STM32") (pin "97") (pinfunction "PE0_97") (pintype "bidirectional"))
      (node (ref "SV2") (pin "34") (pinfunction "34_34") (pintype "passive"))
    )
    (net (code "71") (name "/PE1") (class "Default")
      (node (ref "STM32") (pin "98") (pinfunction "PE1_98") (pintype "bidirectional"))
      (node (ref "SV2") (pin "33") (pinfunction "33_33") (pintype "passive"))
    )
    (net (code "72") (name "/PE2") (class "Default")
      (node (ref "R13") (pin "2") (pinfunction "2_2") (pintype "passive"))
      (node (ref "STM32") (pin "1") (pinfunction "PE2_1") (pintype "bidirectional"))
    )
    (net (code "73") (name "/PE3") (class "Default")
      (node (ref "STM32") (pin "2") (pinfunction "PE3_2") (pintype "bidirectional"))
      (node (ref "SV2") (pin "36") (pinfunction "36_36") (pintype "passive"))
    )
    (net (code "74") (name "/PE4") (class "Default")
      (node (ref "STM32") (pin "3") (pinfunction "PE4_3") (pintype "bidirectional"))
      (node (ref "SV2") (pin "35") (pinfunction "35_35") (pintype "passive"))
    )
    (net (code "75") (name "/PE5") (class "Default")
      (node (ref "STM32") (pin "4") (pinfunction "PE5_4") (pintype "bidirectional"))
      (node (ref "SV2") (pin "38") (pinfunction "38_38") (pintype "passive"))
    )
    (net (code "76") (name "/PE6") (class "Default")
      (node (ref "STM32") (pin "5") (pinfunction "PE6_5") (pintype "bidirectional"))
      (node (ref "SV2") (pin "37") (pinfunction "37_37") (pintype "passive"))
    )
    (net (code "77") (name "/PE7") (class "Default")
      (node (ref "STM32") (pin "38") (pinfunction "PE7_38") (pintype "bidirectional"))
      (node (ref "SV1") (pin "18") (pinfunction "18_18") (pintype "passive"))
    )
    (net (code "78") (name "/PE8") (class "Default")
      (node (ref "STM32") (pin "39") (pinfunction "PE8_39") (pintype "bidirectional"))
      (node (ref "SV1") (pin "17") (pinfunction "17_17") (pintype "passive"))
    )
    (net (code "79") (name "/PE9") (class "Default")
      (node (ref "STM32") (pin "40") (pinfunction "PE9_40") (pintype "bidirectional"))
      (node (ref "SV1") (pin "16") (pinfunction "16_16") (pintype "passive"))
    )
    (net (code "80") (name "/PE10") (class "Default")
      (node (ref "STM32") (pin "41") (pinfunction "PE10_41") (pintype "bidirectional"))
      (node (ref "SV1") (pin "15") (pinfunction "15_15") (pintype "passive"))
    )
    (net (code "81") (name "/PE11") (class "Default")
      (node (ref "STM32") (pin "42") (pinfunction "PE11_42") (pintype "bidirectional"))
      (node (ref "SV1") (pin "14") (pinfunction "14_14") (pintype "passive"))
    )
    (net (code "82") (name "/PE12") (class "Default")
      (node (ref "STM32") (pin "43") (pinfunction "PE12_43") (pintype "bidirectional"))
      (node (ref "SV1") (pin "13") (pinfunction "13_13") (pintype "passive"))
    )
    (net (code "83") (name "/PE13") (class "Default")
      (node (ref "STM32") (pin "44") (pinfunction "PE13_44") (pintype "bidirectional"))
      (node (ref "SV1") (pin "12") (pinfunction "12_12") (pintype "passive"))
    )
    (net (code "84") (name "/PE14") (class "Default")
      (node (ref "STM32") (pin "45") (pinfunction "PE14_45") (pintype "bidirectional"))
      (node (ref "SV1") (pin "11") (pinfunction "11_11") (pintype "passive"))
    )
    (net (code "85") (name "/PE15") (class "Default")
      (node (ref "STM32") (pin "46") (pinfunction "PE15_46") (pintype "bidirectional"))
      (node (ref "SV1") (pin "10") (pinfunction "10_10") (pintype "passive"))
    )
    (net (code "86") (name "/RESET") (class "Default")
      (node (ref "C1") (pin "2") (pinfunction "P$2_2") (pintype "passive"))
      (node (ref "JTAG") (pin "15") (pinfunction "15_15") (pintype "passive"))
      (node (ref "R31") (pin "2") (pinfunction "2_2") (pintype "passive"))
      (node (ref "RESET") (pin "1") (pinfunction "1_1") (pintype "passive"))
      (node (ref "STM32") (pin "14") (pinfunction "NRST_14") (pintype "bidirectional"))
    )
    (net (code "87") (name "/RXD0") (class "Default")
      (node (ref "JP2") (pin "9") (pinfunction "9_9") (pintype "passive"))
      (node (ref "R15") (pin "1") (pinfunction "1_1") (pintype "passive"))
      (node (ref "U2") (pin "8") (pinfunction "RXD0_8") (pintype "bidirectional"))
    )
    (net (code "88") (name "/RXD1") (class "Default")
      (node (ref "JP2") (pin "12") (pinfunction "12_12") (pintype "passive"))
      (node (ref "R14") (pin "1") (pinfunction "1_1") (pintype "passive"))
      (node (ref "U2") (pin "7") (pinfunction "RXD1_7") (pintype "bidirectional"))
    )
    (net (code "89") (name "/RXER") (class "Default")
      (node (ref "JP2") (pin "10") (pinfunction "10_10") (pintype "passive"))
      (node (ref "U2") (pin "10") (pinfunction "RXER_10") (pintype "bidirectional"))
    )
    (net (code "90") (name "/TXD0") (class "Default")
      (node (ref "JP2") (pin "1") (pinfunction "1_1") (pintype "passive"))
      (node (ref "R19") (pin "1") (pinfunction "1_1") (pintype "passive"))
      (node (ref "U2") (pin "17") (pinfunction "TXD0_17") (pintype "bidirectional"))
    )
    (net (code "91") (name "/TXD1") (class "Default")
      (node (ref "JP2") (pin "2") (pinfunction "2_2") (pintype "passive"))
      (node (ref "R17") (pin "1") (pinfunction "1_1") (pintype "passive"))
      (node (ref "U2") (pin "18") (pinfunction "TXD1_18") (pintype "bidirectional"))
    )
    (net (code "92") (name "/TXEN") (class "Default")
      (node (ref "JP2") (pin "4") (pinfunction "4_4") (pintype "passive"))
      (node (ref "R16") (pin "1") (pinfunction "1_1") (pintype "passive"))
      (node (ref "U2") (pin "16") (pinfunction "TXEN_16") (pintype "bidirectional"))
    )
    (net (code "93") (name "/VBAT") (class "Default")
      (node (ref "R38") (pin "2") (pinfunction "2_2") (pintype "passive"))
      (node (ref "STM32") (pin "6") (pinfunction "VBAT_6") (pintype "bidirectional"))
    )
    (net (code "94") (name "/VDDA") (class "Default")
      (node (ref "C13") (pin "1") (pinfunction "P$1_1") (pintype "passive"))
      (node (ref "C22") (pin "1") (pinfunction "P$1_1") (pintype "passive"))
      (node (ref "L3") (pin "2") (pinfunction "2_2") (pintype "passive"))
      (node (ref "R29") (pin "1") (pinfunction "1_1") (pintype "passive"))
      (node (ref "STM32") (pin "22") (pinfunction "VDDA_22") (pintype "bidirectional"))
    )
    (net (code "95") (name "/VIN") (class "Default")
      (node (ref "D1") (pin "C") (pinfunction "-_C") (pintype "passive"))
      (node (ref "JP1") (pin "3") (pinfunction "3_3") (pintype "bidirectional"))
      (node (ref "R40") (pin "1") (pinfunction "1_1") (pintype "passive"))
      (node (ref "SV2") (pin "1") (pinfunction "1_1") (pintype "passive"))
      (node (ref "SV2") (pin "2") (pinfunction "2_2") (pintype "passive"))
    )
    (net (code "96") (name "/VREF+") (class "Default")
      (node (ref "C28") (pin "1") (pinfunction "P$1_1") (pintype "passive"))
      (node (ref "R29") (pin "2") (pinfunction "2_2") (pintype "passive"))
      (node (ref "STM32") (pin "21") (pinfunction "VREF+_21") (pintype "bidirectional"))
    )
    (net (code "97") (name "/VREF-") (class "Default")
      (node (ref "C28") (pin "2") (pinfunction "P$2_2") (pintype "passive"))
      (node (ref "R28") (pin "2") (pinfunction "2_2") (pintype "passive"))
      (node (ref "STM32") (pin "20") (pinfunction "VSSA_20") (pintype "bidirectional"))
    )
    (net (code "98") (name "3.3V") (class "Default")
      (node (ref "BOOT/USART3") (pin "4") (pinfunction "4_4") (pintype "passive"))
      (node (ref "C10") (pin "1") (pinfunction "P$1_1") (pintype "passive"))
      (node (ref "C16") (pin "2") (pinfunction "P$2_2") (pintype "passive"))
      (node (ref "C23") (pin "+") (pinfunction "+_+") (pintype "passive"))
      (node (ref "C24") (pin "+") (pinfunction "+_+") (pintype "passive"))
      (node (ref "C30") (pin "1") (pinfunction "P$1_1") (pintype "passive"))
      (node (ref "C34") (pin "1") (pinfunction "P$1_1") (pintype "passive"))
      (node (ref "C35") (pin "1") (pinfunction "P$1_1") (pintype "passive"))
      (node (ref "C38") (pin "1") (pinfunction "P$1_1") (pintype "passive"))
      (node (ref "C39") (pin "1") (pinfunction "P$1_1") (pintype "passive"))
      (node (ref "C40") (pin "1") (pinfunction "P$1_1") (pintype "passive"))
      (node (ref "C41") (pin "+") (pinfunction "+_+") (pintype "passive"))
      (node (ref "C42") (pin "1") (pinfunction "P$1_1") (pintype "passive"))
      (node (ref "JP1") (pin "2") (pinfunction "2_2") (pintype "bidirectional"))
      (node (ref "JP2") (pin "11") (pinfunction "11_11") (pintype "passive"))
      (node (ref "JTAG") (pin "1") (pinfunction "1_1") (pintype "passive"))
      (node (ref "JTAG") (pin "2") (pinfunction "2_2") (pintype "passive"))
      (node (ref "L1") (pin "2") (pinfunction "2_2") (pintype "passive"))
      (node (ref "L3") (pin "1") (pinfunction "1_1") (pintype "passive"))
      (node (ref "R10") (pin "2") (pinfunction "2_2") (pintype "passive"))
      (node (ref "R11") (pin "2") (pinfunction "2_2") (pintype "passive"))
      (node (ref "R18") (pin "2") (pinfunction "2_2") (pintype "passive"))
      (node (ref "R23") (pin "1") (pinfunction "1_1") (pintype "passive"))
      (node (ref "R31") (pin "1") (pinfunction "1_1") (pintype "passive"))
      (node (ref "R36") (pin "2") (pinfunction "2_2") (pintype "passive"))
      (node (ref "R37") (pin "2") (pinfunction "2_2") (pintype "passive"))
      (node (ref "R38") (pin "1") (pinfunction "1_1") (pintype "passive"))
      (node (ref "R39") (pin "1") (pinfunction "1_1") (pintype "passive"))
      (node (ref "R45") (pin "1") (pinfunction "1_1") (pintype "passive"))
      (node (ref "R48") (pin "2") (pinfunction "2_2") (pintype "passive"))
      (node (ref "R49") (pin "2") (pinfunction "2_2") (pintype "passive"))
      (node (ref "R52") (pin "1") (pinfunction "1_1") (pintype "passive"))
      (node (ref "R7") (pin "2") (pinfunction "2_2") (pintype "passive"))
      (node (ref "R9") (pin "1") (pinfunction "1_1") (pintype "passive"))
      (node (ref "S1") (pin "2") (pinfunction "S_2") (pintype "passive"))
      (node (ref "STM32") (pin "100") (pinfunction "VDD6_100") (pintype "bidirectional"))
      (node (ref "STM32") (pin "11") (pinfunction "VDD_11") (pintype "bidirectional"))
      (node (ref "STM32") (pin "19") (pinfunction "VDD2_19") (pintype "bidirectional"))
      (node (ref "STM32") (pin "28") (pinfunction "VDD3_28") (pintype "bidirectional"))
      (node (ref "STM32") (pin "50") (pinfunction "VDD4_50") (pintype "bidirectional"))
      (node (ref "STM32") (pin "75") (pinfunction "VDD5_75") (pintype "bidirectional"))
      (node (ref "SV1") (pin "19") (pinfunction "19_19") (pintype "passive"))
      (node (ref "SV1") (pin "20") (pinfunction "20_20") (pintype "passive"))
      (node (ref "SV1") (pin "35") (pinfunction "35_35") (pintype "passive"))
      (node (ref "SV1") (pin "36") (pinfunction "36_36") (pintype "passive"))
      (node (ref "SV2") (pin "3") (pinfunction "3_3") (pintype "passive"))
      (node (ref "SV2") (pin "4") (pinfunction "4_4") (pintype "passive"))
      (node (ref "U2") (pin "9") (pinfunction "VDDIO_9") (pintype "bidirectional"))
    )
    (net (code "99") (name "GND") (class "Default")
      (node (ref "3.3V_LED") (pin "C") (pinfunction "C_C") (pintype "passive"))
      (node (ref "BOOT/USART3") (pin "3") (pinfunction "3_3") (pintype "passive"))
      (node (ref "C1") (pin "1") (pinfunction "P$1_1") (pintype "passive"))
      (node (ref "C10") (pin "2") (pinfunction "P$2_2") (pintype "passive"))
      (node (ref "C11") (pin "1") (pinfunction "P$1_1") (pintype "passive"))
      (node (ref "C12") (pin "1") (pinfunction "P$1_1") (pintype "passive"))
      (node (ref "C13") (pin "2") (pinfunction "P$2_2") (pintype "passive"))
      (node (ref "C14") (pin "+") (pinfunction "+_+") (pintype "passive"))
      (node (ref "C15") (pin "2") (pinfunction "P$2_2") (pintype "passive"))
      (node (ref "C16") (pin "1") (pinfunction "P$1_1") (pintype "passive"))
      (node (ref "C17") (pin "2") (pinfunction "P$2_2") (pintype "passive"))
      (node (ref "C19") (pin "2") (pinfunction "P$2_2") (pintype "passive"))
      (node (ref "C2") (pin "2") (pinfunction "P$2_2") (pintype "passive"))
      (node (ref "C20") (pin "2") (pinfunction "P$2_2") (pintype "passive"))
      (node (ref "C21") (pin "2") (pinfunction "P$2_2") (pintype "passive"))
      (node (ref "C22") (pin "2") (pinfunction "P$2_2") (pintype "passive"))
      (node (ref "C23") (pin "-") (pinfunction "-_-") (pintype "passive"))
      (node (ref "C24") (pin "-") (pinfunction "-_-") (pintype "passive"))
      (node (ref "C25") (pin "2") (pinfunction "P$2_2") (pintype "passive"))
      (node (ref "C26") (pin "2") (pinfunction "P$2_2") (pintype "passive"))
      (node (ref "C27") (pin "2") (pinfunction "P$2_2") (pintype "passive"))
      (node (ref "C29") (pin "2") (pinfunction "P$2_2") (pintype "passive"))
      (node (ref "C3") (pin "2") (pinfunction "P$2_2") (pintype "passive"))
      (node (ref "C30") (pin "2") (pinfunction "P$2_2") (pintype "passive"))
      (node (ref "C34") (pin "2") (pinfunction "P$2_2") (pintype "passive"))
      (node (ref "C35") (pin "2") (pinfunction "P$2_2") (pintype "passive"))
      (node (ref "C38") (pin "2") (pinfunction "P$2_2") (pintype "passive"))
      (node (ref "C39") (pin "2") (pinfunction "P$2_2") (pintype "passive"))
      (node (ref "C4") (pin "-") (pinfunction "-_-") (pintype "passive"))
      (node (ref "C40") (pin "2") (pinfunction "P$2_2") (pintype "passive"))
      (node (ref "C41") (pin "-") (pinfunction "-_-") (pintype "passive"))
      (node (ref "C42") (pin "2") (pinfunction "P$2_2") (pintype "passive"))
      (node (ref "C5") (pin "2") (pinfunction "P$2_2") (pintype "passive"))
      (node (ref "C6") (pin "-") (pinfunction "-_-") (pintype "passive"))
      (node (ref "C7") (pin "1") (pinfunction "P$1_1") (pintype "passive"))
      (node (ref "C8") (pin "1") (pinfunction "P$1_1") (pintype "passive"))
      (node (ref "C9") (pin "2") (pinfunction "P$2_2") (pintype "passive"))
      (node (ref "CN1") (pin "GND") (pinfunction "GND_GND") (pintype "power_in"))
      (node (ref "JP1") (pin "1") (pinfunction "1_1") (pintype "bidirectional"))
      (node (ref "JP2") (pin "13") (pinfunction "13_13") (pintype "passive"))
      (node (ref "JP2") (pin "14") (pinfunction "14_14") (pintype "passive"))
      (node (ref "JTAG") (pin "10") (pinfunction "10_10") (pintype "passive"))
      (node (ref "JTAG") (pin "12") (pinfunction "12_12") (pintype "passive"))
      (node (ref "JTAG") (pin "14") (pinfunction "14_14") (pintype "passive"))
      (node (ref "JTAG") (pin "16") (pinfunction "16_16") (pintype "passive"))
      (node (ref "JTAG") (pin "18") (pinfunction "18_18") (pintype "passive"))
      (node (ref "JTAG") (pin "20") (pinfunction "20_20") (pintype "passive"))
      (node (ref "JTAG") (pin "4") (pinfunction "4_4") (pintype "passive"))
      (node (ref "JTAG") (pin "6") (pinfunction "6_6") (pintype "passive"))
      (node (ref "JTAG") (pin "8") (pinfunction "8_8") (pintype "passive"))
      (node (ref "LED1") (pin "K") (pinfunction "C_K") (pintype "passive"))
      (node (ref "LED2") (pin "K") (pinfunction "C_K") (pintype "passive"))
      (node (ref "LED3") (pin "C") (pinfunction "C_C") (pintype "passive"))
      (node (ref "Q4") (pin "2") (pinfunction "S_2") (pintype "bidirectional"))
      (node (ref "Q5") (pin "2") (pinfunction "S_2") (pintype "bidirectional"))
      (node (ref "R28") (pin "1") (pinfunction "1_1") (pintype "passive"))
      (node (ref "R42") (pin "2") (pinfunction "2_2") (pintype "passive"))
      (node (ref "R44") (pin "2") (pinfunction "2_2") (pintype "passive"))
      (node (ref "R5") (pin "2") (pinfunction "2_2") (pintype "passive"))
      (node (ref "R51") (pin "1") (pinfunction "1_1") (pintype "passive"))
      (node (ref "R6") (pin "2") (pinfunction "2_2") (pintype "passive"))
      (node (ref "RESET") (pin "2") (pinfunction "2_2") (pintype "passive"))
      (node (ref "STAT_LED1") (pin "C") (pinfunction "C_C") (pintype "passive"))
      (node (ref "STAT_LED2") (pin "C") (pinfunction "C_C") (pintype "passive"))
      (node (ref "STM32") (pin "10") (pinfunction "VSS_10") (pintype "bidirectional"))
      (node (ref "STM32") (pin "27") (pinfunction "VSS2_27") (pintype "bidirectional"))
      (node (ref "STM32") (pin "74") (pinfunction "VSS3_74") (pintype "bidirectional"))
      (node (ref "STM32") (pin "99") (pinfunction "VSS4_99") (pintype "bidirectional"))
      (node (ref "SV1") (pin "1") (pinfunction "1_1") (pintype "passive"))
      (node (ref "SV1") (pin "2") (pinfunction "2_2") (pintype "passive"))
      (node (ref "SV1") (pin "21") (pinfunction "21_21") (pintype "passive"))
      (node (ref "SV1") (pin "22") (pinfunction "22_22") (pintype "passive"))
      (node (ref "SV1") (pin "3") (pinfunction "3_3") (pintype "passive"))
      (node (ref "SV1") (pin "33") (pinfunction "33_33") (pintype "passive"))
      (node (ref "SV1") (pin "34") (pinfunction "34_34") (pintype "passive"))
      (node (ref "SV1") (pin "7") (pinfunction "7_7") (pintype "passive"))
      (node (ref "SV1") (pin "8") (pinfunction "8_8") (pintype "passive"))
      (node (ref "SV1") (pin "9") (pinfunction "9_9") (pintype "passive"))
      (node (ref "SV2") (pin "10") (pinfunction "10_10") (pintype "passive"))
      (node (ref "SV2") (pin "13") (pinfunction "13_13") (pintype "passive"))
      (node (ref "SV2") (pin "14") (pinfunction "14_14") (pintype "passive"))
      (node (ref "SV2") (pin "31") (pinfunction "31_31") (pintype "passive"))
      (node (ref "SV2") (pin "32") (pinfunction "32_32") (pintype "passive"))
      (node (ref "SV2") (pin "5") (pinfunction "5_5") (pintype "passive"))
      (node (ref "SV2") (pin "6") (pinfunction "6_6") (pintype "passive"))
      (node (ref "U1") (pin "1") (pinfunction "P$1_1") (pintype "bidirectional"))
      (node (ref "U2") (pin "THERM") (pinfunction "GND_THERM") (pintype "bidirectional"))
      (node (ref "VIN_LED") (pin "C") (pinfunction "C_C") (pintype "passive"))
      (node (ref "X1") (pin "1") (pinfunction "1_1") (pintype "power_in"))
      (node (ref "X1") (pin "3") (pinfunction "3_3") (pintype "power_in"))
    )
    (net (code "100") (name "GND1") (class "Default")
      (node (ref "C14") (pin "-") (pinfunction "-_-") (pintype "passive"))
      (node (ref "RJ1") (pin "GND") (pinfunction "GND_GND") (pintype "bidirectional"))
      (node (ref "RJ1") (pin "SHIELD0") (pinfunction "SHIELD0_SHIELD0") (pintype "bidirectional"))
      (node (ref "RJ1") (pin "SHIELD1") (pinfunction "SHIELD1_SHIELD1") (pintype "bidirectional"))
    )
    (net (code "101") (name "LED1") (class "Default")
      (node (ref "Q5") (pin "1") (pinfunction "G_1") (pintype "bidirectional"))
      (node (ref "U2") (pin "3") (pinfunction "LED1/REGOFF_3") (pintype "bidirectional"))
    )
    (net (code "102") (name "LED2") (class "Default")
      (node (ref "Q4") (pin "1") (pinfunction "G_1") (pintype "bidirectional"))
      (node (ref "R6") (pin "1") (pinfunction "1_1") (pintype "passive"))
      (node (ref "U2") (pin "2") (pinfunction "LED2/NINTSEL_2") (pintype "bidirectional"))
    )
    (net (code "103") (name "Net-(3.3V_LED-PadA)") (class "Default")
      (node (ref "3.3V_LED") (pin "A") (pinfunction "A_A") (pintype "passive"))
      (node (ref "R7") (pin "1") (pinfunction "1_1") (pintype "passive"))
    )
    (net (code "104") (name "Net-(C2-P$1)") (class "Default")
      (node (ref "C2") (pin "1") (pinfunction "P$1_1") (pintype "passive"))
      (node (ref "C3") (pin "1") (pinfunction "P$1_1") (pintype "passive"))
      (node (ref "C4") (pin "+") (pinfunction "+_+") (pintype "passive"))
      (node (ref "R18") (pin "1") (pinfunction "1_1") (pintype "passive"))
      (node (ref "U1") (pin "2") (pinfunction "P$2_2") (pintype "bidirectional"))
      (node (ref "U1") (pin "4") (pinfunction "P$4_4") (pintype "bidirectional"))
    )
    (net (code "105") (name "Net-(C7-P$2)") (class "Default")
      (node (ref "C7") (pin "2") (pinfunction "P$2_2") (pintype "passive"))
      (node (ref "Q2") (pin "1") (pinfunction "1_1") (pintype "passive"))
      (node (ref "R34") (pin "1") (pinfunction "1_1") (pintype "passive"))
      (node (ref "R35") (pin "2") (pinfunction "2_2") (pintype "passive"))
    )
    (net (code "106") (name "Net-(C19-P$1)") (class "Default")
      (node (ref "C19") (pin "1") (pinfunction "P$1_1") (pintype "passive"))
      (node (ref "STM32") (pin "73") (pinfunction "VCAP_2_73") (pintype "bidirectional"))
    )
    (net (code "107") (name "Net-(C20-P$1)") (class "Default")
      (node (ref "C20") (pin "1") (pinfunction "P$1_1") (pintype "passive"))
      (node (ref "STM32") (pin "49") (pinfunction "VCAP_1_49") (pintype "bidirectional"))
    )
    (net (code "108") (name "Net-(CN1-PadD+)") (class "Default")
      (node (ref "CN1") (pin "D+") (pinfunction "D+_D+") (pintype "bidirectional"))
      (node (ref "R3") (pin "1") (pinfunction "1_1") (pintype "passive"))
    )
    (net (code "109") (name "Net-(CN1-PadD-)") (class "Default")
      (node (ref "CN1") (pin "D-") (pinfunction "D-_D-") (pintype "bidirectional"))
      (node (ref "R2") (pin "1") (pinfunction "1_1") (pintype "passive"))
    )
    (net (code "110") (name "Net-(CN1-PadID)") (class "Default")
      (node (ref "CN1") (pin "ID") (pinfunction "ID_ID") (pintype "bidirectional"))
      (node (ref "R24") (pin "1") (pinfunction "1_1") (pintype "passive"))
    )
    (net (code "111") (name "Net-(CN1-PadVBUS)") (class "Default")
      (node (ref "CN1") (pin "VBUS") (pinfunction "VBUS_VBUS") (pintype "power_in"))
      (node (ref "R41") (pin "1") (pinfunction "1_1") (pintype "passive"))
    )
    (net (code "112") (name "Net-(D1-+)") (class "Default")
      (node (ref "D1") (pin "A") (pinfunction "+_A") (pintype "passive"))
      (node (ref "X1") (pin "2") (pinfunction "2_2") (pintype "power_in"))
    )
    (net (code "113") (name "Net-(LED1-PadA)") (class "Default")
      (node (ref "LED1") (pin "A") (pinfunction "A_A") (pintype "passive"))
      (node (ref "R32") (pin "2") (pinfunction "2_2") (pintype "passive"))
      (node (ref "STAT_LED1") (pin "A") (pinfunction "A_A") (pintype "passive"))
    )
    (net (code "114") (name "Net-(LED2-PadA)") (class "Default")
      (node (ref "LED2") (pin "A") (pinfunction "A_A") (pintype "passive"))
      (node (ref "R33") (pin "2") (pinfunction "2_2") (pintype "passive"))
      (node (ref "STAT_LED2") (pin "A") (pinfunction "A_A") (pintype "passive"))
    )
    (net (code "115") (name "Net-(LED3-PadA)") (class "Default")
      (node (ref "LED3") (pin "A") (pinfunction "A_A") (pintype "passive"))
      (node (ref "R30") (pin "2") (pinfunction "2_2") (pintype "passive"))
    )
    (net (code "116") (name "Net-(Q4-D)") (class "Default")
      (node (ref "Q4") (pin "3") (pinfunction "D_3") (pintype "bidirectional"))
      (node (ref "RJ1") (pin "G-") (pinfunction "G-_G-") (pintype "bidirectional"))
    )
    (net (code "117") (name "Net-(Q5-D)") (class "Default")
      (node (ref "Q5") (pin "3") (pinfunction "D_3") (pintype "bidirectional"))
      (node (ref "RJ1") (pin "Y-") (pinfunction "Y-_Y-") (pintype "bidirectional"))
    )
    (net (code "118") (name "Net-(R1-Pad1)") (class "Default")
      (node (ref "R1") (pin "1") (pinfunction "1_1") (pintype "passive"))
      (node (ref "VIN_LED") (pin "A") (pinfunction "A_A") (pintype "passive"))
    )
    (net (code "119") (name "Net-(R10-Pad1)") (class "Default")
      (node (ref "R10") (pin "1") (pinfunction "1_1") (pintype "passive"))
      (node (ref "RJ1") (pin "G+") (pinfunction "G+_G+") (pintype "bidirectional"))
    )
    (net (code "120") (name "Net-(R11-Pad1)") (class "Default")
      (node (ref "R11") (pin "1") (pinfunction "1_1") (pintype "passive"))
      (node (ref "RJ1") (pin "Y+") (pinfunction "Y+_Y+") (pintype "bidirectional"))
    )
    (net (code "121") (name "Net-(S1-P)") (class "Default")
      (node (ref "R43") (pin "2") (pinfunction "2_2") (pintype "passive"))
      (node (ref "R44") (pin "1") (pinfunction "1_1") (pintype "passive"))
      (node (ref "S1") (pin "1") (pinfunction "P_1") (pintype "passive"))
    )
    (net (code "122") (name "Net-(U2-RBIAS)") (class "Default")
      (node (ref "R5") (pin "1") (pinfunction "1_1") (pintype "passive"))
      (node (ref "U2") (pin "24") (pinfunction "RBIAS_24") (pintype "bidirectional"))
    )
    (net (code "123") (name "RX_N") (class "Default")
      (node (ref "R27") (pin "2") (pinfunction "2_2") (pintype "passive"))
      (node (ref "RJ1") (pin "RD-") (pinfunction "RD-_RD-") (pintype "bidirectional"))
      (node (ref "U2") (pin "22") (pinfunction "RX-_22") (pintype "bidirectional"))
    )
    (net (code "124") (name "RX_P") (class "Default")
      (node (ref "R26") (pin "2") (pinfunction "2_2") (pintype "passive"))
      (node (ref "RJ1") (pin "RD+") (pinfunction "RD+_RD+") (pintype "bidirectional"))
      (node (ref "U2") (pin "23") (pinfunction "RX+_23") (pintype "bidirectional"))
    )
    (net (code "125") (name "TX_N") (class "Default")
      (node (ref "R25") (pin "2") (pinfunction "2_2") (pintype "passive"))
      (node (ref "RJ1") (pin "TD-") (pinfunction "TD-_TD-") (pintype "bidirectional"))
      (node (ref "U2") (pin "20") (pinfunction "TX-_20") (pintype "bidirectional"))
    )
    (net (code "126") (name "TX_P") (class "Default")
      (node (ref "R8") (pin "2") (pinfunction "2_2") (pintype "passive"))
      (node (ref "RJ1") (pin "TD+") (pinfunction "TD+_TD+") (pintype "bidirectional"))
      (node (ref "U2") (pin "21") (pinfunction "TX+_21") (pintype "bidirectional"))
    )
    (net (code "127") (name "USB_DET") (class "Default")
      (node (ref "R41") (pin "2") (pinfunction "2_2") (pintype "passive"))
      (node (ref "STM32") (pin "68") (pinfunction "PA9_68") (pintype "bidirectional"))
    )
    (net (code "128") (name "USB_ID") (class "Default")
      (node (ref "R24") (pin "2") (pinfunction "2_2") (pintype "passive"))
      (node (ref "STM32") (pin "69") (pinfunction "PA10_69") (pintype "bidirectional"))
    )
    (net (code "129") (name "USB_N") (class "Default")
      (node (ref "R2") (pin "2") (pinfunction "2_2") (pintype "passive"))
      (node (ref "STM32") (pin "70") (pinfunction "PA11_70") (pintype "bidirectional"))
    )
    (net (code "130") (name "USB_P") (class "Default")
      (node (ref "R3") (pin "2") (pinfunction "2_2") (pintype "passive"))
      (node (ref "STM32") (pin "71") (pinfunction "PA12_71") (pintype "bidirectional"))
    )
    (net (code "131") (name "VDDA_PHY") (class "Default")
      (node (ref "C15") (pin "1") (pinfunction "P$1_1") (pintype "passive"))
      (node (ref "C25") (pin "1") (pinfunction "P$1_1") (pintype "passive"))
      (node (ref "C26") (pin "1") (pinfunction "P$1_1") (pintype "passive"))
      (node (ref "C27") (pin "1") (pinfunction "P$1_1") (pintype "passive"))
      (node (ref "C29") (pin "1") (pinfunction "P$1_1") (pintype "passive"))
      (node (ref "L1") (pin "1") (pinfunction "1_1") (pintype "passive"))
      (node (ref "R25") (pin "1") (pinfunction "1_1") (pintype "passive"))
      (node (ref "R26") (pin "1") (pinfunction "1_1") (pintype "passive"))
      (node (ref "R27") (pin "1") (pinfunction "1_1") (pintype "passive"))
      (node (ref "R8") (pin "1") (pinfunction "1_1") (pintype "passive"))
      (node (ref "RJ1") (pin "P4") (pinfunction "P4_P4") (pintype "bidirectional"))
      (node (ref "RJ1") (pin "P5") (pinfunction "P5_P5") (pintype "bidirectional"))
      (node (ref "U2") (pin "1") (pinfunction "VDD2A_1") (pintype "bidirectional"))
      (node (ref "U2") (pin "19") (pinfunction "VDD1A_19") (pintype "bidirectional"))
    )
    (net (code "132") (name "VDDCR") (class "Default")
      (node (ref "C17") (pin "1") (pinfunction "P$1_1") (pintype "passive"))
      (node (ref "C21") (pin "1") (pinfunction "P$1_1") (pintype "passive"))
      (node (ref "U2") (pin "6") (pinfunction "VDDCR_6") (pintype "bidirectional"))
    )
    (net (code "133") (name "XTAL1") (class "Default")
      (node (ref "C12") (pin "2") (pinfunction "P$2_2") (pintype "passive"))
      (node (ref "Q3") (pin "2") (pinfunction "2_2") (pintype "passive"))
      (node (ref "R4") (pin "2") (pinfunction "2_2") (pintype "passive"))
      (node (ref "U2") (pin "5") (pinfunction "XTAL1_5") (pintype "bidirectional"))
    )
    (net (code "134") (name "XTAL2") (class "Default")
      (node (ref "C11") (pin "2") (pinfunction "P$2_2") (pintype "passive"))
      (node (ref "Q3") (pin "1") (pinfunction "1_1") (pintype "passive"))
      (node (ref "R4") (pin "1") (pinfunction "1_1") (pintype "passive"))
      (node (ref "U2") (pin "4") (pinfunction "XTAL2_4") (pintype "bidirectional"))
    )
    (net (code "135") (name "unconnected-(H1-Pad1)") (class "Default")
      (node (ref "H1") (pin "1") (pinfunction "1_1") (pintype "passive"))
    )
    (net (code "136") (name "unconnected-(H2-Pad1)") (class "Default")
      (node (ref "H2") (pin "1") (pinfunction "1_1") (pintype "passive"))
    )
    (net (code "137") (name "unconnected-(H3-Pad1)") (class "Default")
      (node (ref "H3") (pin "1") (pinfunction "1_1") (pintype "passive"))
    )
    (net (code "138") (name "unconnected-(H4-Pad1)") (class "Default")
      (node (ref "H4") (pin "1") (pinfunction "1_1") (pintype "passive"))
    )
    (net (code "139") (name "unconnected-(H5-Pad1)") (class "Default")
      (node (ref "H5") (pin "1") (pinfunction "1_1") (pintype "passive"))
    )
    (net (code "140") (name "unconnected-(H6-Pad1)") (class "Default")
      (node (ref "H6") (pin "1") (pinfunction "1_1") (pintype "passive"))
    )
    (net (code "141") (name "unconnected-(JTAG-Pad11)") (class "Default")
      (node (ref "JTAG") (pin "11") (pinfunction "11_11") (pintype "passive"))
    )
    (net (code "142") (name "unconnected-(JTAG-Pad17)") (class "Default")
      (node (ref "JTAG") (pin "17") (pinfunction "17_17") (pintype "passive"))
    )
    (net (code "143") (name "unconnected-(JTAG-Pad19)") (class "Default")
      (node (ref "JTAG") (pin "19") (pinfunction "19_19") (pintype "passive"))
    )
    (net (code "144") (name "unconnected-(RJ1-PadNC)") (class "Default")
      (node (ref "RJ1") (pin "NC") (pinfunction "NC_NC") (pintype "bidirectional"))
    )
  )
)
